# b_SI_Boost.net
KiCad netlist of a schematic drawn in EAGLE
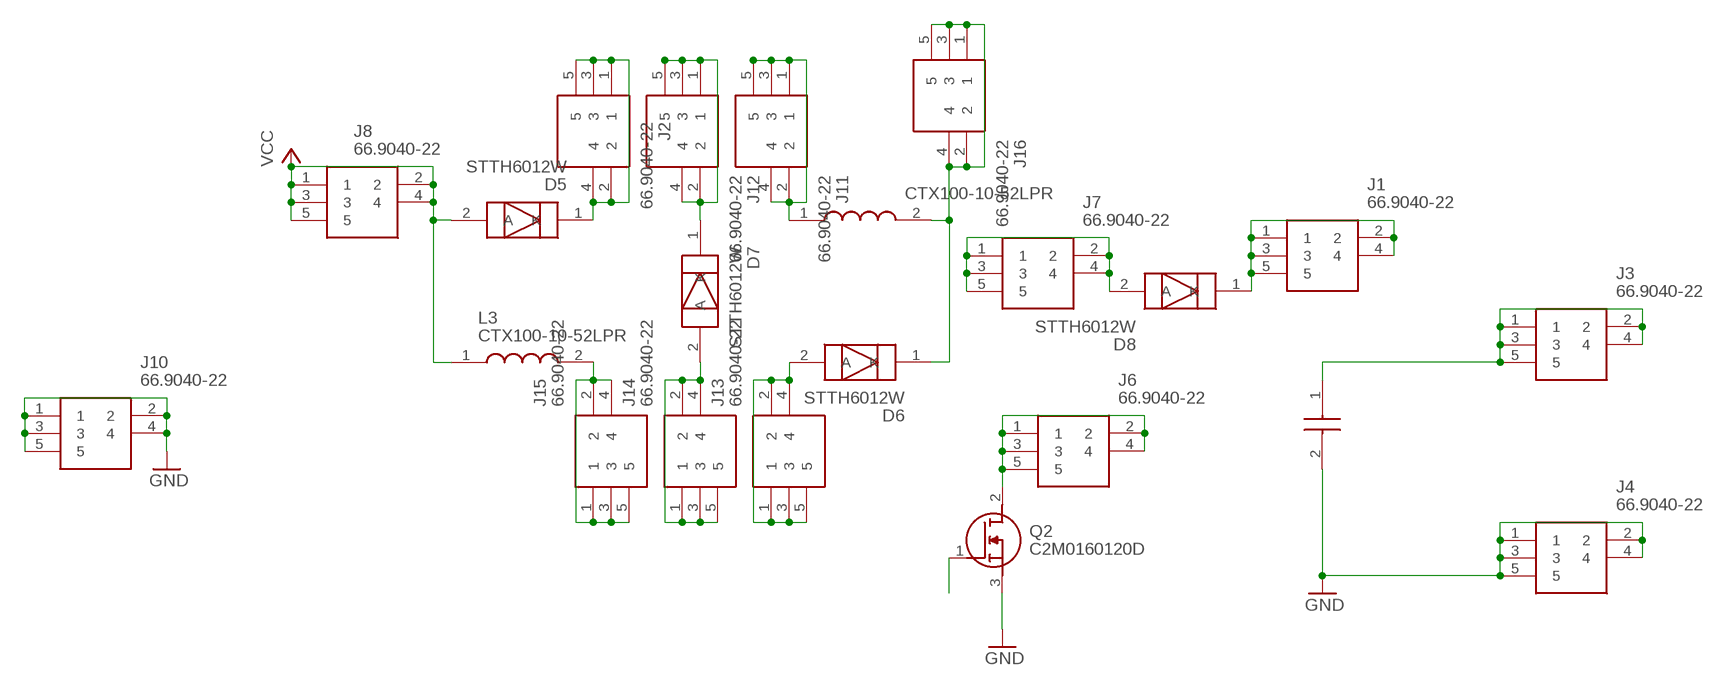
[diagram p0: schematic, sheet 1]

(export (version "E")
  (design (tool "Eeschema 10.0.6"))
  (components
    (comp (ref "D5")
      (value "STTH6012W")
      (footprint "eagle-import:TO1090P515X1560X2445-2P")
      (fields (field (name "RS_PART_NUMBER") "6870818"))
      (libsource (lib "eagle-import") (part "STTH6012W"))
    )
    (comp (ref "D6")
      (value "STTH6012W")
      (footprint "eagle-import:TO1090P515X1560X2445-2P")
      (fields (field (name "RS_PART_NUMBER") "6870818"))
      (libsource (lib "eagle-import") (part "STTH6012W"))
    )
    (comp (ref "D7")
      (value "STTH6012W")
      (footprint "eagle-import:TO1090P515X1560X2445-2P")
      (fields (field (name "RS_PART_NUMBER") "6870818"))
      (libsource (lib "eagle-import") (part "STTH6012W"))
    )
    (comp (ref "D8")
      (value "STTH6012W")
      (footprint "eagle-import:TO1090P515X1560X2445-2P")
      (fields (field (name "RS_PART_NUMBER") "6870818"))
      (libsource (lib "eagle-import") (part "STTH6012W"))
    )
    (comp (ref "J1")
      (value "66.9040-22")
      (footprint "eagle-import:66904022")
      (libsource (lib "eagle-import") (part "66.9040-22"))
    )
    (comp (ref "J2")
      (value "66.9040-22")
      (footprint "eagle-import:66904022")
      (libsource (lib "eagle-import") (part "66.9040-22"))
    )
    (comp (ref "J3")
      (value "66.9040-22")
      (footprint "eagle-import:66904022")
      (libsource (lib "eagle-import") (part "66.9040-22"))
    )
    (comp (ref "J4")
      (value "66.9040-22")
      (footprint "eagle-import:66904022")
      (libsource (lib "eagle-import") (part "66.9040-22"))
    )
    (comp (ref "J6")
      (value "66.9040-22")
      (footprint "eagle-import:66904022")
      (libsource (lib "eagle-import") (part "66.9040-22"))
    )
    (comp (ref "J7")
      (value "66.9040-22")
      (footprint "eagle-import:66904022")
      (libsource (lib "eagle-import") (part "66.9040-22"))
    )
    (comp (ref "J8")
      (value "66.9040-22")
      (footprint "eagle-import:66904022")
      (libsource (lib "eagle-import") (part "66.9040-22"))
    )
    (comp (ref "J10")
      (value "66.9040-22")
      (footprint "eagle-import:66904022")
      (libsource (lib "eagle-import") (part "66.9040-22"))
    )
    (comp (ref "J11")
      (value "66.9040-22")
      (footprint "eagle-import:66904022")
      (libsource (lib "eagle-import") (part "66.9040-22"))
    )
    (comp (ref "J12")
      (value "66.9040-22")
      (footprint "eagle-import:66904022")
      (libsource (lib "eagle-import") (part "66.9040-22"))
    )
    (comp (ref "J13")
      (value "66.9040-22")
      (footprint "eagle-import:66904022")
      (libsource (lib "eagle-import") (part "66.9040-22"))
    )
    (comp (ref "J14")
      (value "66.9040-22")
      (footprint "eagle-import:66904022")
      (libsource (lib "eagle-import") (part "66.9040-22"))
    )
    (comp (ref "J15")
      (value "66.9040-22")
      (footprint "eagle-import:66904022")
      (libsource (lib "eagle-import") (part "66.9040-22"))
    )
    (comp (ref "J16")
      (value "66.9040-22")
      (footprint "eagle-import:66904022")
      (libsource (lib "eagle-import") (part "66.9040-22"))
    )
    (comp (ref "L3")
      (value "CTX100-10-52LPR")
      (footprint "eagle-import:CTX1001052LPR")
      (libsource (lib "eagle-import") (part "CTX100-10-52LPR"))
    )
    (comp (ref "L4")
      (value "CTX100-10-52LPR")
      (footprint "eagle-import:CTX1001052LPR")
      (libsource (lib "eagle-import") (part "CTX100-10-52LPR"))
    )
    (comp (ref "Q2")
      (value "C2M0160120D")
      (footprint "eagle-import:TO544P521X1594X2550-3P")
      (fields (field (name "RS_PART_NUMBER") "1629709"))
      (libsource (lib "eagle-import") (part "C2M0160120D"))
    )
    (comp (ref "U$1")
      (value "B32774D4505K000")
      (footprint "eagle-import:B32774D4505K000")
      (fields (field (name "RS_PART_NUMBER") "1726009"))
      (libsource (lib "eagle-import") (part "B32774D4505K000"))
    )
  )
  (nets
    (net (code "1") (name "GND") (class "Default")
      (node (ref "J10") (pin "1") (pinfunction "1_1") (pintype "bidirectional"))
      (node (ref "J10") (pin "2") (pinfunction "2_2") (pintype "bidirectional"))
      (node (ref "J10") (pin "3") (pinfunction "3_3") (pintype "bidirectional"))
      (node (ref "J10") (pin "4") (pinfunction "4_4") (pintype "bidirectional"))
      (node (ref "J10") (pin "5") (pinfunction "5_5") (pintype "bidirectional"))
      (node (ref "J4") (pin "1") (pinfunction "1_1") (pintype "bidirectional"))
      (node (ref "J4") (pin "2") (pinfunction "2_2") (pintype "bidirectional"))
      (node (ref "J4") (pin "3") (pinfunction "3_3") (pintype "bidirectional"))
      (node (ref "J4") (pin "4") (pinfunction "4_4") (pintype "bidirectional"))
      (node (ref "J4") (pin "5") (pinfunction "5_5") (pintype "bidirectional"))
      (node (ref "Q2") (pin "3") (pinfunction "S_3") (pintype "bidirectional"))
      (node (ref "U$1") (pin "2") (pinfunction "2_2") (pintype "bidirectional"))
    )
    (net (code "2") (name "Net-(D5-K)") (class "Default")
      (node (ref "D5") (pin "1") (pinfunction "K_1") (pintype "bidirectional"))
      (node (ref "J2") (pin "1") (pinfunction "1_1") (pintype "bidirectional"))
      (node (ref "J2") (pin "2") (pinfunction "2_2") (pintype "bidirectional"))
      (node (ref "J2") (pin "3") (pinfunction "3_3") (pintype "bidirectional"))
      (node (ref "J2") (pin "4") (pinfunction "4_4") (pintype "bidirectional"))
      (node (ref "J2") (pin "5") (pinfunction "5_5") (pintype "bidirectional"))
    )
    (net (code "3") (name "Net-(D6-A)") (class "Default")
      (node (ref "D6") (pin "2") (pinfunction "A_2") (pintype "bidirectional"))
      (node (ref "J13") (pin "1") (pinfunction "1_1") (pintype "bidirectional"))
      (node (ref "J13") (pin "2") (pinfunction "2_2") (pintype "bidirectional"))
      (node (ref "J13") (pin "3") (pinfunction "3_3") (pintype "bidirectional"))
      (node (ref "J13") (pin "4") (pinfunction "4_4") (pintype "bidirectional"))
      (node (ref "J13") (pin "5") (pinfunction "5_5") (pintype "bidirectional"))
    )
    (net (code "4") (name "Net-(D6-K)") (class "Default")
      (node (ref "D6") (pin "1") (pinfunction "K_1") (pintype "bidirectional"))
      (node (ref "J16") (pin "1") (pinfunction "1_1") (pintype "bidirectional"))
      (node (ref "J16") (pin "2") (pinfunction "2_2") (pintype "bidirectional"))
      (node (ref "J16") (pin "3") (pinfunction "3_3") (pintype "bidirectional"))
      (node (ref "J16") (pin "4") (pinfunction "4_4") (pintype "bidirectional"))
      (node (ref "J16") (pin "5") (pinfunction "5_5") (pintype "bidirectional"))
      (node (ref "L4") (pin "2") (pinfunction "2_2") (pintype "bidirectional"))
    )
    (net (code "5") (name "Net-(D7-A)") (class "Default")
      (node (ref "D7") (pin "2") (pinfunction "A_2") (pintype "bidirectional"))
      (node (ref "J14") (pin "1") (pinfunction "1_1") (pintype "bidirectional"))
      (node (ref "J14") (pin "2") (pinfunction "2_2") (pintype "bidirectional"))
      (node (ref "J14") (pin "3") (pinfunction "3_3") (pintype "bidirectional"))
      (node (ref "J14") (pin "4") (pinfunction "4_4") (pintype "bidirectional"))
      (node (ref "J14") (pin "5") (pinfunction "5_5") (pintype "bidirectional"))
    )
    (net (code "6") (name "Net-(D7-K)") (class "Default")
      (node (ref "D7") (pin "1") (pinfunction "K_1") (pintype "bidirectional"))
      (node (ref "J12") (pin "1") (pinfunction "1_1") (pintype "bidirectional"))
      (node (ref "J12") (pin "2") (pinfunction "2_2") (pintype "bidirectional"))
      (node (ref "J12") (pin "3") (pinfunction "3_3") (pintype "bidirectional"))
      (node (ref "J12") (pin "4") (pinfunction "4_4") (pintype "bidirectional"))
      (node (ref "J12") (pin "5") (pinfunction "5_5") (pintype "bidirectional"))
    )
    (net (code "7") (name "Net-(D8-A)") (class "Default")
      (node (ref "D8") (pin "2") (pinfunction "A_2") (pintype "bidirectional"))
      (node (ref "J7") (pin "1") (pinfunction "1_1") (pintype "bidirectional"))
      (node (ref "J7") (pin "2") (pinfunction "2_2") (pintype "bidirectional"))
      (node (ref "J7") (pin "3") (pinfunction "3_3") (pintype "bidirectional"))
      (node (ref "J7") (pin "4") (pinfunction "4_4") (pintype "bidirectional"))
      (node (ref "J7") (pin "5") (pinfunction "5_5") (pintype "bidirectional"))
    )
    (net (code "8") (name "Net-(D8-K)") (class "Default")
      (node (ref "D8") (pin "1") (pinfunction "K_1") (pintype "bidirectional"))
      (node (ref "J1") (pin "1") (pinfunction "1_1") (pintype "bidirectional"))
      (node (ref "J1") (pin "2") (pinfunction "2_2") (pintype "bidirectional"))
      (node (ref "J1") (pin "3") (pinfunction "3_3") (pintype "bidirectional"))
      (node (ref "J1") (pin "4") (pinfunction "4_4") (pintype "bidirectional"))
      (node (ref "J1") (pin "5") (pinfunction "5_5") (pintype "bidirectional"))
    )
    (net (code "9") (name "Net-(J3-Pad1)") (class "Default")
      (node (ref "J3") (pin "1") (pinfunction "1_1") (pintype "bidirectional"))
      (node (ref "J3") (pin "2") (pinfunction "2_2") (pintype "bidirectional"))
      (node (ref "J3") (pin "3") (pinfunction "3_3") (pintype "bidirectional"))
      (node (ref "J3") (pin "4") (pinfunction "4_4") (pintype "bidirectional"))
      (node (ref "J3") (pin "5") (pinfunction "5_5") (pintype "bidirectional"))
      (node (ref "U$1") (pin "1") (pinfunction "1_1") (pintype "bidirectional"))
    )
    (net (code "10") (name "Net-(J11-Pad1)") (class "Default")
      (node (ref "J11") (pin "1") (pinfunction "1_1") (pintype "bidirectional"))
      (node (ref "J11") (pin "2") (pinfunction "2_2") (pintype "bidirectional"))
      (node (ref "J11") (pin "3") (pinfunction "3_3") (pintype "bidirectional"))
      (node (ref "J11") (pin "4") (pinfunction "4_4") (pintype "bidirectional"))
      (node (ref "J11") (pin "5") (pinfunction "5_5") (pintype "bidirectional"))
      (node (ref "L4") (pin "1") (pinfunction "1_1") (pintype "bidirectional"))
    )
    (net (code "11") (name "Net-(J15-Pad1)") (class "Default")
      (node (ref "J15") (pin "1") (pinfunction "1_1") (pintype "bidirectional"))
      (node (ref "J15") (pin "2") (pinfunction "2_2") (pintype "bidirectional"))
      (node (ref "J15") (pin "3") (pinfunction "3_3") (pintype "bidirectional"))
      (node (ref "J15") (pin "4") (pinfunction "4_4") (pintype "bidirectional"))
      (node (ref "J15") (pin "5") (pinfunction "5_5") (pintype "bidirectional"))
      (node (ref "L3") (pin "2") (pinfunction "2_2") (pintype "bidirectional"))
    )
    (net (code "12") (name "Net-(Q2-D)") (class "Default")
      (node (ref "J6") (pin "1") (pinfunction "1_1") (pintype "bidirectional"))
      (node (ref "J6") (pin "2") (pinfunction "2_2") (pintype "bidirectional"))
      (node (ref "J6") (pin "3") (pinfunction "3_3") (pintype "bidirectional"))
      (node (ref "J6") (pin "4") (pinfunction "4_4") (pintype "bidirectional"))
      (node (ref "J6") (pin "5") (pinfunction "5_5") (pintype "bidirectional"))
      (node (ref "Q2") (pin "2") (pinfunction "D_2") (pintype "bidirectional"))
    )
    (net (code "13") (name "VCC") (class "Default")
      (node (ref "D5") (pin "2") (pinfunction "A_2") (pintype "bidirectional"))
      (node (ref "J8") (pin "1") (pinfunction "1_1") (pintype "bidirectional"))
      (node (ref "J8") (pin "2") (pinfunction "2_2") (pintype "bidirectional"))
      (node (ref "J8") (pin "3") (pinfunction "3_3") (pintype "bidirectional"))
      (node (ref "J8") (pin "4") (pinfunction "4_4") (pintype "bidirectional"))
      (node (ref "J8") (pin "5") (pinfunction "5_5") (pintype "bidirectional"))
      (node (ref "L3") (pin "1") (pinfunction "1_1") (pintype "bidirectional"))
    )
    (net (code "14") (name "unconnected-(Q2-G-Pad1)") (class "Default")
      (node (ref "Q2") (pin "1") (pinfunction "G_1") (pintype "bidirectional"))
    )
  )
)
